# 2014_FDP_PROPULSION.net
KiCad netlist of a schematic drawn in Altium Designer
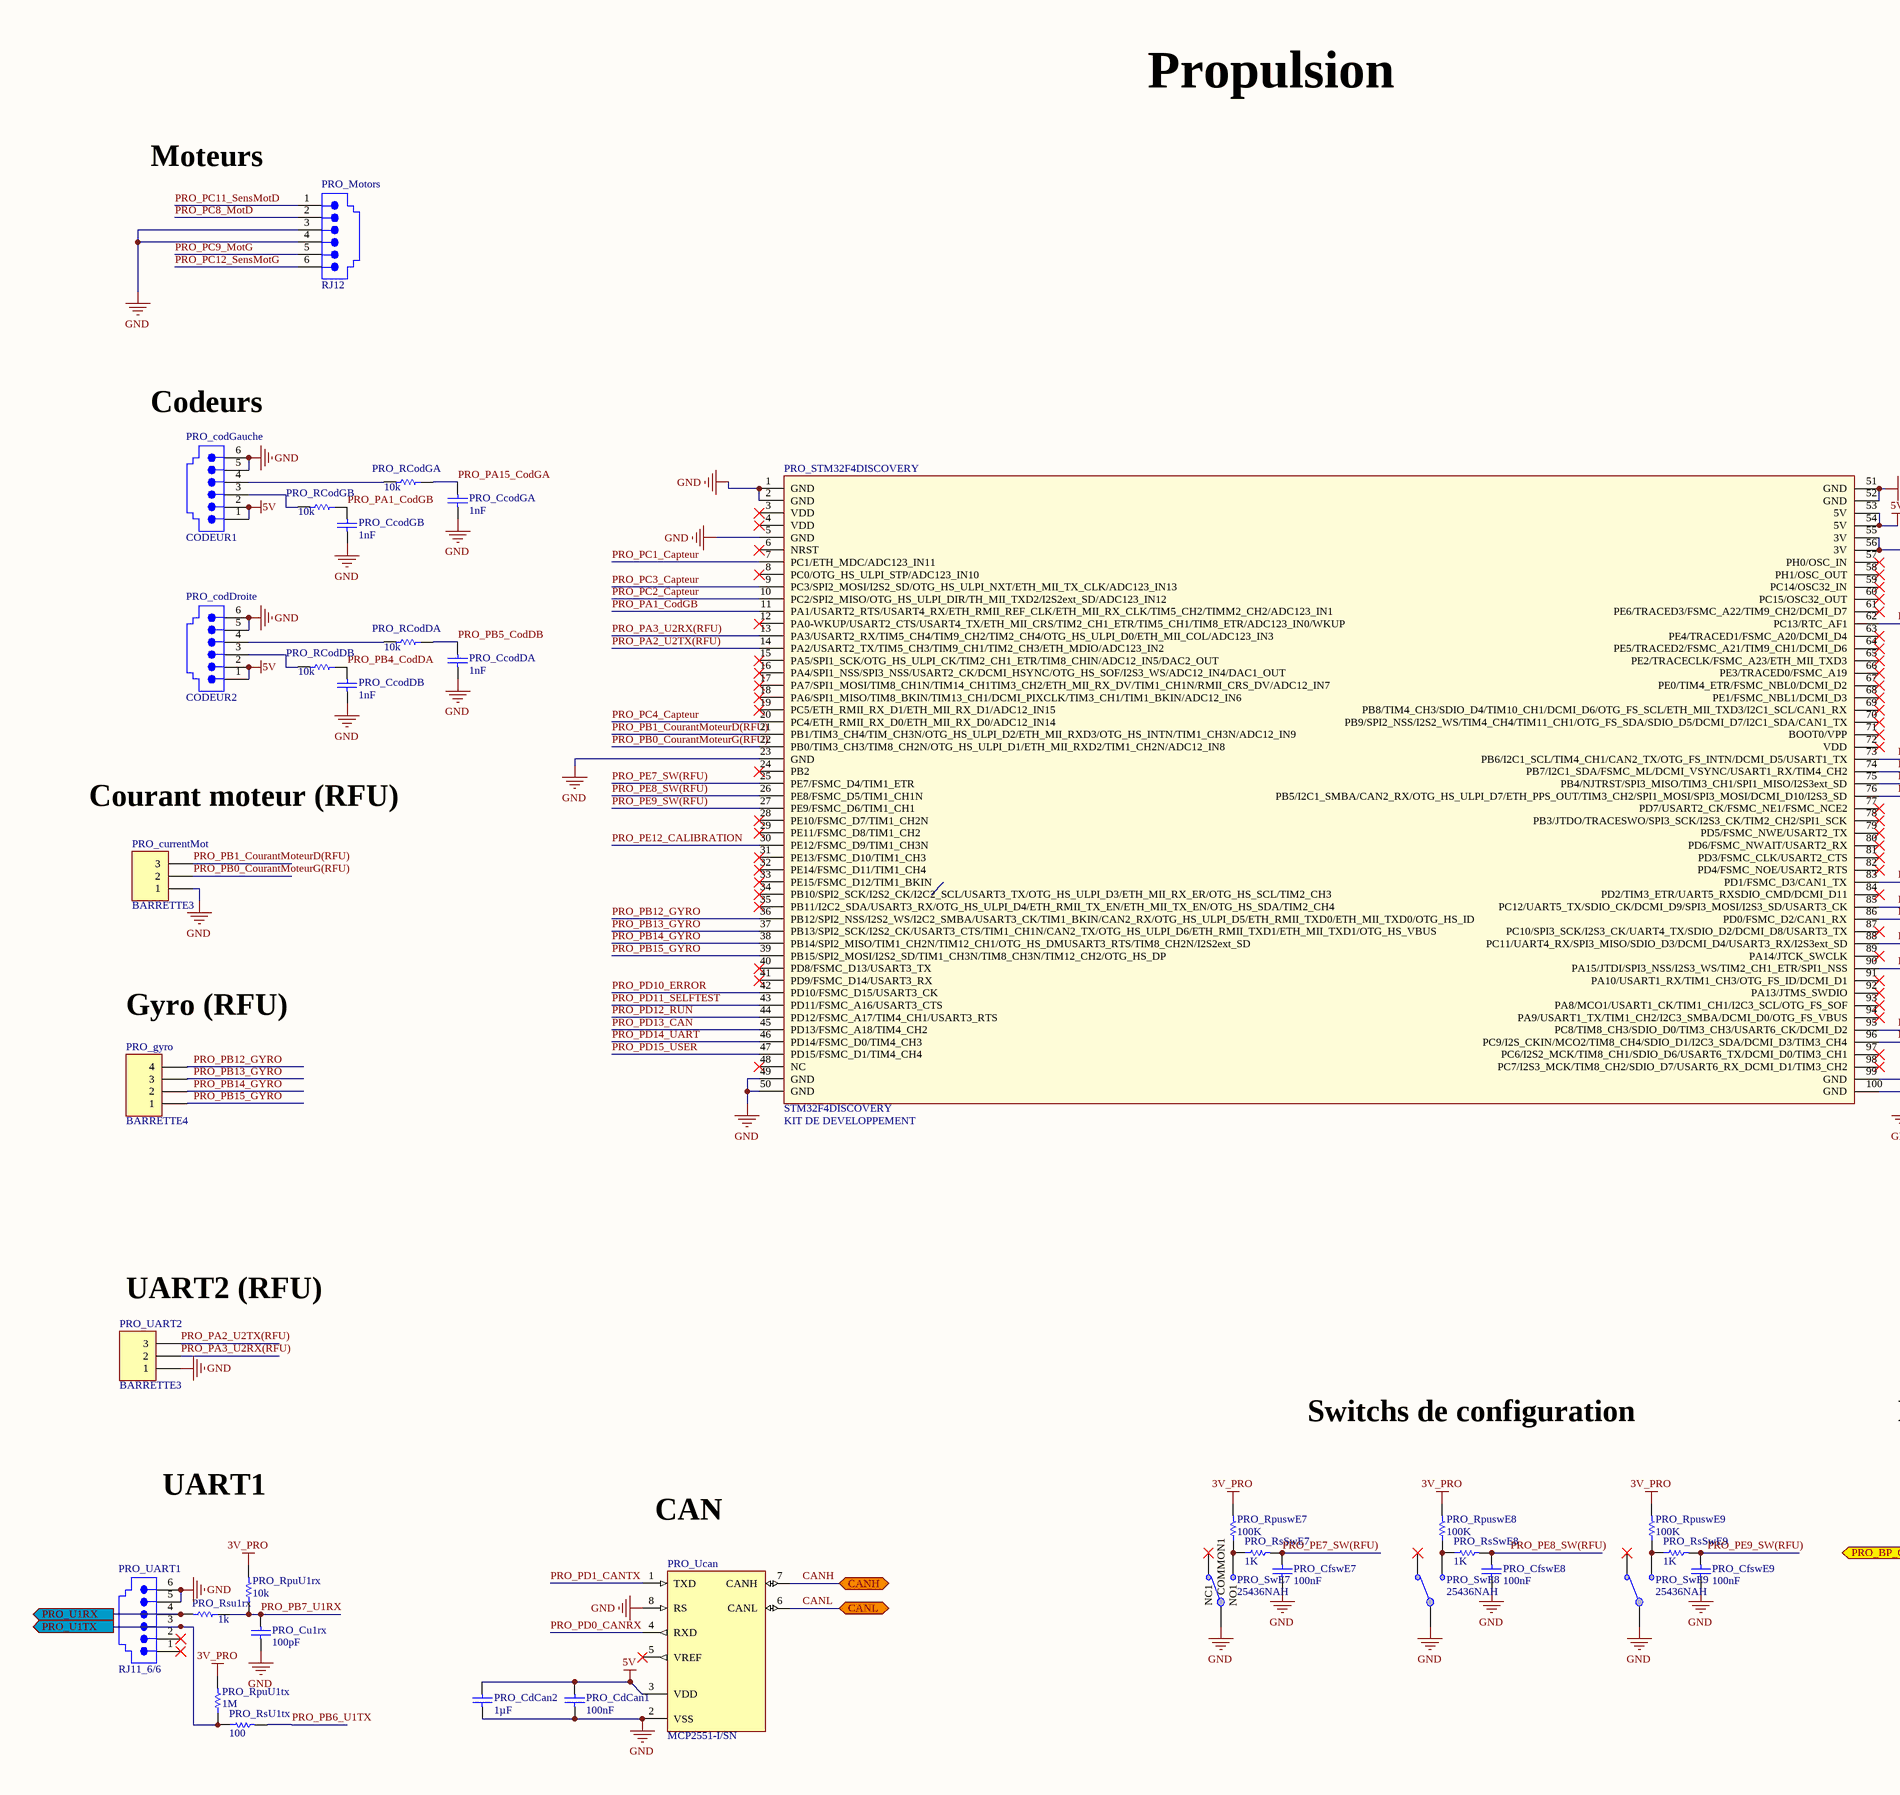
[diagram p0: 2014_FDP_PROPULSION.SchDoc, left]
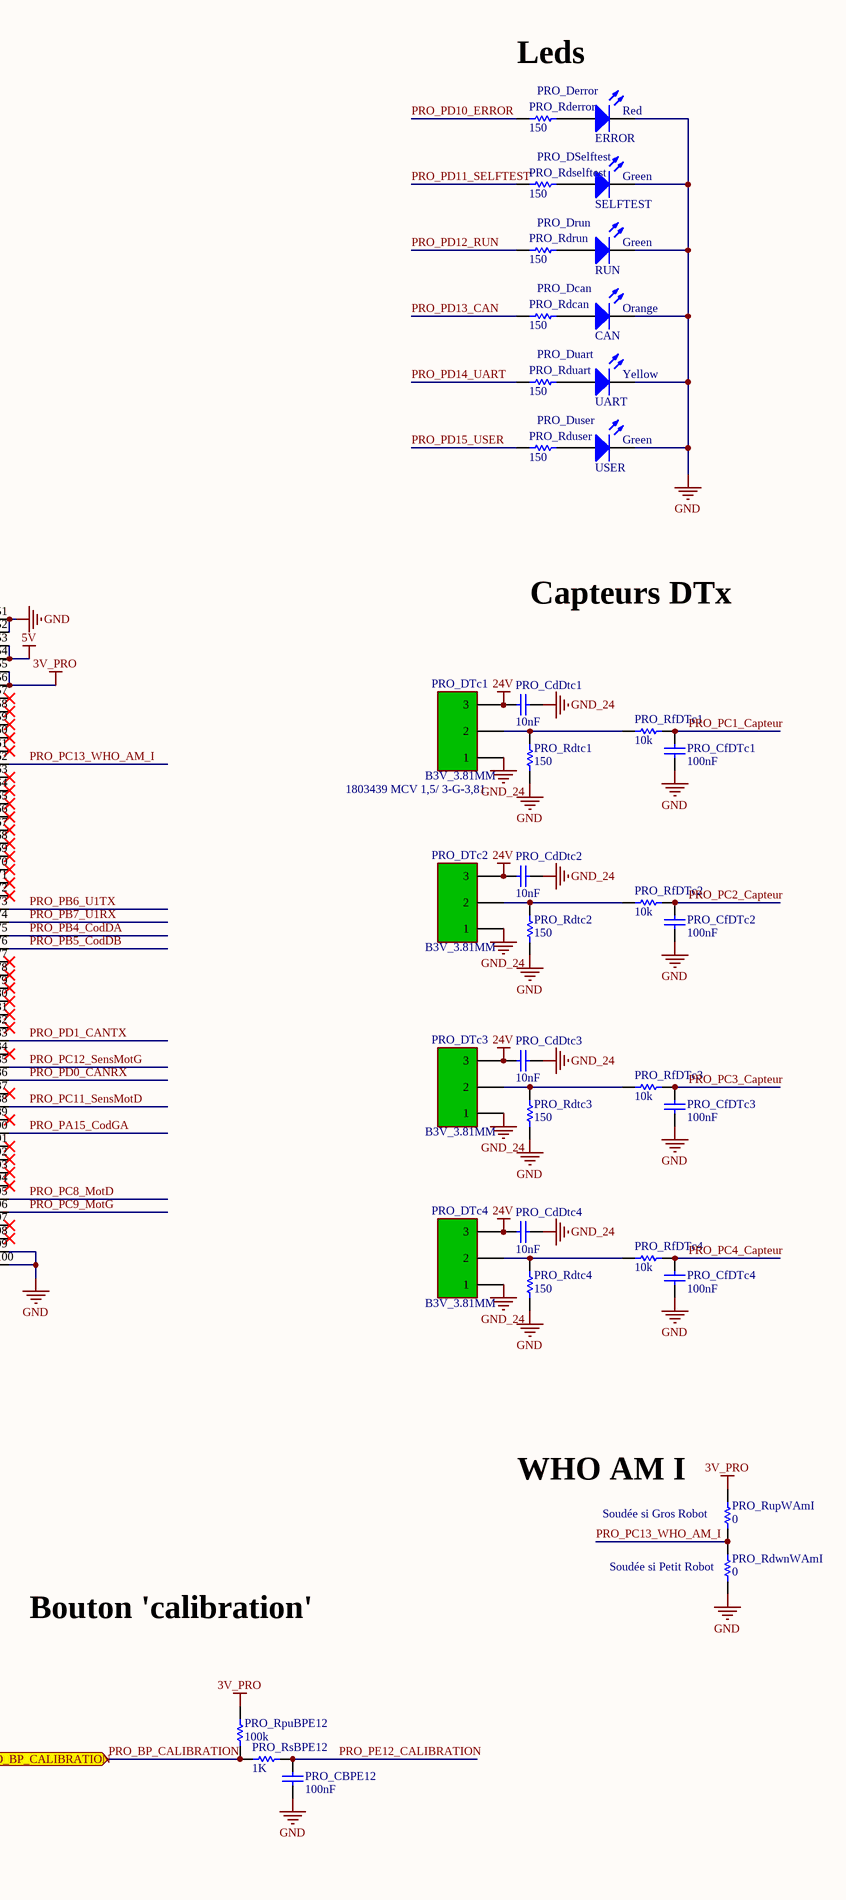
[diagram p1: 2014_FDP_PROPULSION.SchDoc, right]

(export (version "E")
  (design (tool "Eeschema 10.0.6"))
  (components
    (comp (ref "PRO_CBPE12")
      (value "100nF")
      (footprint "C0805_N")
      (description "Capacitor")
      (fields (field (name "PUBLISHER") "Altium Limited"))
      (libsource (lib "_ROBOT") (part "Condensateur"))
    )
    (comp (ref "PRO_CcodDA")
      (value "1nF")
      (footprint "C0805_N")
      (description "Capacitor")
      (fields (field (name "PUBLISHER") "Altium Limited"))
      (libsource (lib "_ROBOT") (part "Condensateur"))
    )
    (comp (ref "PRO_CcodDB")
      (value "1nF")
      (footprint "C0805_N")
      (description "Capacitor")
      (fields (field (name "PUBLISHER") "Altium Limited"))
      (libsource (lib "_ROBOT") (part "Condensateur"))
    )
    (comp (ref "PRO_CcodGA")
      (value "1nF")
      (footprint "C0805_N")
      (description "Capacitor")
      (fields (field (name "PUBLISHER") "Altium Limited"))
      (libsource (lib "_ROBOT") (part "Condensateur"))
    )
    (comp (ref "PRO_CcodGB")
      (value "1nF")
      (footprint "C0805_N")
      (description "Capacitor")
      (fields (field (name "PUBLISHER") "Altium Limited"))
      (libsource (lib "_ROBOT") (part "Condensateur"))
    )
    (comp (ref "PRO_CdCan1")
      (value "100nF")
      (footprint "C0805_N")
      (description "Capacitor")
      (fields (field (name "PUBLISHER") "Altium Limited"))
      (libsource (lib "_ROBOT") (part "Condensateur"))
    )
    (comp (ref "PRO_CdCan2")
      (value "1µF")
      (footprint "C0805_N")
      (description "Capacitor")
      (fields (field (name "PUBLISHER") "Altium Limited"))
      (libsource (lib "_ROBOT") (part "Condensateur"))
    )
    (comp (ref "PRO_CdDtc1")
      (value "10nF")
      (footprint "C0805_N")
      (description "Capacitor")
      (fields (field (name "PUBLISHER") "Altium Limited"))
      (libsource (lib "_ROBOT") (part "Condensateur"))
    )
    (comp (ref "PRO_CdDtc2")
      (value "10nF")
      (footprint "C0805_N")
      (description "Capacitor")
      (fields (field (name "PUBLISHER") "Altium Limited"))
      (libsource (lib "_ROBOT") (part "Condensateur"))
    )
    (comp (ref "PRO_CdDtc3")
      (value "10nF")
      (footprint "C0805_N")
      (description "Capacitor")
      (fields (field (name "PUBLISHER") "Altium Limited"))
      (libsource (lib "_ROBOT") (part "Condensateur"))
    )
    (comp (ref "PRO_CdDtc4")
      (value "10nF")
      (footprint "C0805_N")
      (description "Capacitor")
      (fields (field (name "PUBLISHER") "Altium Limited"))
      (libsource (lib "_ROBOT") (part "Condensateur"))
    )
    (comp (ref "PRO_CfDTc1")
      (value "100nF")
      (footprint "C0805_N")
      (description "Capacitor")
      (fields (field (name "PUBLISHER") "Altium Limited"))
      (libsource (lib "_ROBOT") (part "Condensateur"))
    )
    (comp (ref "PRO_CfDTc2")
      (value "100nF")
      (footprint "C0805_N")
      (description "Capacitor")
      (fields (field (name "PUBLISHER") "Altium Limited"))
      (libsource (lib "_ROBOT") (part "Condensateur"))
    )
    (comp (ref "PRO_CfDTc3")
      (value "100nF")
      (footprint "C0805_N")
      (description "Capacitor")
      (fields (field (name "PUBLISHER") "Altium Limited"))
      (libsource (lib "_ROBOT") (part "Condensateur"))
    )
    (comp (ref "PRO_CfDTc4")
      (value "100nF")
      (footprint "C0805_N")
      (description "Capacitor")
      (fields (field (name "PUBLISHER") "Altium Limited"))
      (libsource (lib "_ROBOT") (part "Condensateur"))
    )
    (comp (ref "PRO_CfswE7")
      (value "100nF")
      (footprint "C0805_N")
      (description "Capacitor")
      (fields (field (name "PUBLISHER") "Altium Limited"))
      (libsource (lib "_ROBOT") (part "Condensateur"))
    )
    (comp (ref "PRO_CfswE8")
      (value "100nF")
      (footprint "C0805_N")
      (description "Capacitor")
      (fields (field (name "PUBLISHER") "Altium Limited"))
      (libsource (lib "_ROBOT") (part "Condensateur"))
    )
    (comp (ref "PRO_CfswE9")
      (value "100nF")
      (footprint "C0805_N")
      (description "Capacitor")
      (fields (field (name "PUBLISHER") "Altium Limited"))
      (libsource (lib "_ROBOT") (part "Condensateur"))
    )
    (comp (ref "PRO_codDroite")
      (value "CODEUR2")
      (footprint "RJ11_6/6 - droit")
      (description "Right Angle, Standard Profile, Offset Latch DECconnect, Flangeless PCB Jack")
      (fields (field (name "PUBLISHER") "Altium Limited"))
      (libsource (lib "miniprojet") (part "RJ11_6/6"))
    )
    (comp (ref "PRO_codGauche")
      (value "CODEUR1")
      (footprint "RJ11_6/6 - droit")
      (description "Right Angle, Standard Profile, Offset Latch DECconnect, Flangeless PCB Jack")
      (fields (field (name "PUBLISHER") "Altium Limited"))
      (libsource (lib "miniprojet") (part "RJ11_6/6"))
    )
    (comp (ref "PRO_Cu1rx")
      (value "100pF")
      (footprint "C0805_N")
      (description "Capacitor")
      (fields (field (name "PUBLISHER") "Altium Limited"))
      (libsource (lib "_ROBOT") (part "Condensateur"))
    )
    (comp (ref "PRO_currentMot")
      (value "BARRETTE3")
      (footprint "HE14_3")
      (description "Header, 3-Pin")
      (fields (field (name "PUBLISHER") "Altium Limited"))
      (libsource (lib "Connecteur") (part "BARRETTE3"))
    )
    (comp (ref "PRO_Dcan")
      (value "CAN")
      (footprint "LED_0805")
      (description "Typical LED")
      (fields (field (name "PUBLISHER") "Altium Limited"))
      (libsource (lib "_ROBOT") (part "LED"))
    )
    (comp (ref "PRO_Derror")
      (value "ERROR")
      (footprint "LED_0805")
      (description "Typical LED")
      (fields (field (name "PUBLISHER") "Altium Limited"))
      (libsource (lib "_ROBOT") (part "LED"))
    )
    (comp (ref "PRO_Drun")
      (value "RUN")
      (footprint "LED_0805")
      (description "Typical LED")
      (fields (field (name "PUBLISHER") "Altium Limited"))
      (libsource (lib "_ROBOT") (part "LED"))
    )
    (comp (ref "PRO_DSelftest")
      (value "SELFTEST")
      (footprint "LED_0805")
      (description "Typical LED")
      (fields (field (name "PUBLISHER") "Altium Limited"))
      (libsource (lib "_ROBOT") (part "LED"))
    )
    (comp (ref "PRO_DTc1")
      (value "B3V_3.81MM")
      (footprint "BORNIER_3V_3.81MM")
      (fields (field (name "REF") "1803439 MCV 1,5/ 3-G-3,81"))
      (libsource (lib "Connecteur") (part "BORNIER_3V_3.81MM"))
    )
    (comp (ref "PRO_DTc2")
      (value "B3V_3.81MM")
      (footprint "BORNIER_3V_3.81MM")
      (libsource (lib "Connecteur") (part "BORNIER_3V_3.81MM"))
    )
    (comp (ref "PRO_DTc3")
      (value "B3V_3.81MM")
      (footprint "BORNIER_3V_3.81MM")
      (libsource (lib "Connecteur") (part "BORNIER_3V_3.81MM"))
    )
    (comp (ref "PRO_DTc4")
      (value "B3V_3.81MM")
      (footprint "BORNIER_3V_3.81MM")
      (libsource (lib "Connecteur") (part "BORNIER_3V_3.81MM"))
    )
    (comp (ref "PRO_Duart")
      (value "UART")
      (footprint "LED_0805")
      (description "Typical LED")
      (fields (field (name "PUBLISHER") "Altium Limited"))
      (libsource (lib "_ROBOT") (part "LED"))
    )
    (comp (ref "PRO_Duser")
      (value "USER")
      (footprint "LED_0805")
      (description "Typical LED")
      (fields (field (name "PUBLISHER") "Altium Limited"))
      (libsource (lib "_ROBOT") (part "LED"))
    )
    (comp (ref "PRO_gyro")
      (value "BARRETTE4")
      (footprint "HE14_4")
      (description "Header, 4-Pin")
      (fields (field (name "PUBLISHER") "Altium Limited"))
      (libsource (lib "Connecteur") (part "BARRETTE4"))
    )
    (comp (ref "PRO_Motors")
      (value "RJ12")
      (footprint "RJ11_6/6")
      (description "Right Angle, Standard Profile, Offset Latch DECconnect, Flangeless PCB Jack")
      (fields (field (name "PUBLISHER") "Altium Limited"))
      (libsource (lib "Connecteur") (part "RJ11_6/6"))
    )
    (comp (ref "PRO_RCodDA")
      (value "10k")
      (footprint "R1206_N")
      (description "Resistor")
      (fields (field (name "PUBLISHER") "Altium Limited"))
      (libsource (lib "_ROBOT") (part "Resistor"))
    )
    (comp (ref "PRO_RCodDB")
      (value "10k")
      (footprint "R1206_N")
      (description "Resistor")
      (fields (field (name "PUBLISHER") "Altium Limited"))
      (libsource (lib "_ROBOT") (part "Resistor"))
    )
    (comp (ref "PRO_RCodGA")
      (value "10k")
      (footprint "R1206_N")
      (description "Resistor")
      (fields (field (name "PUBLISHER") "Altium Limited"))
      (libsource (lib "_ROBOT") (part "Resistor"))
    )
    (comp (ref "PRO_RCodGB")
      (value "10k")
      (footprint "R1206_N")
      (description "Resistor")
      (fields (field (name "PUBLISHER") "Altium Limited"))
      (libsource (lib "_ROBOT") (part "Resistor"))
    )
    (comp (ref "PRO_Rdcan")
      (value "150")
      (footprint "R1206_N")
      (description "Resistor")
      (fields (field (name "PUBLISHER") "Altium Limited"))
      (libsource (lib "_ROBOT") (part "Resistor"))
    )
    (comp (ref "PRO_Rderror")
      (value "150")
      (footprint "R1206_N")
      (description "Resistor")
      (fields (field (name "PUBLISHER") "Altium Limited"))
      (libsource (lib "_ROBOT") (part "Resistor"))
    )
    (comp (ref "PRO_Rdrun")
      (value "150")
      (footprint "R1206_N")
      (description "Resistor")
      (fields (field (name "PUBLISHER") "Altium Limited"))
      (libsource (lib "_ROBOT") (part "Resistor"))
    )
    (comp (ref "PRO_Rdselftest")
      (value "150")
      (footprint "R1206_N")
      (description "Resistor")
      (fields (field (name "PUBLISHER") "Altium Limited"))
      (libsource (lib "_ROBOT") (part "Resistor"))
    )
    (comp (ref "PRO_Rdtc1")
      (value "150")
      (footprint "R1206_N")
      (description "Resistor")
      (fields (field (name "PUBLISHER") "Altium Limited"))
      (libsource (lib "_ROBOT") (part "Resistor"))
    )
    (comp (ref "PRO_Rdtc2")
      (value "150")
      (footprint "R1206_N")
      (description "Resistor")
      (fields (field (name "PUBLISHER") "Altium Limited"))
      (libsource (lib "_ROBOT") (part "Resistor"))
    )
    (comp (ref "PRO_Rdtc3")
      (value "150")
      (footprint "R1206_N")
      (description "Resistor")
      (fields (field (name "PUBLISHER") "Altium Limited"))
      (libsource (lib "_ROBOT") (part "Resistor"))
    )
    (comp (ref "PRO_Rdtc4")
      (value "150")
      (footprint "R1206_N")
      (description "Resistor")
      (fields (field (name "PUBLISHER") "Altium Limited"))
      (libsource (lib "_ROBOT") (part "Resistor"))
    )
    (comp (ref "PRO_Rduart")
      (value "150")
      (footprint "R1206_N")
      (description "Resistor")
      (fields (field (name "PUBLISHER") "Altium Limited"))
      (libsource (lib "_ROBOT") (part "Resistor"))
    )
    (comp (ref "PRO_Rduser")
      (value "150")
      (footprint "R1206_N")
      (description "Resistor")
      (fields (field (name "PUBLISHER") "Altium Limited"))
      (libsource (lib "_ROBOT") (part "Resistor"))
    )
    (comp (ref "PRO_RdwnWAmI")
      (value "0")
      (footprint "R1206_N")
      (description "Resistor")
      (fields (field (name "PUBLISHER") "Altium Limited"))
      (libsource (lib "_ROBOT") (part "Resistor"))
    )
    (comp (ref "PRO_RfDTc1")
      (value "10k")
      (footprint "R1206_N")
      (description "Resistor")
      (fields (field (name "PUBLISHER") "Altium Limited"))
      (libsource (lib "_ROBOT") (part "Resistor"))
    )
    (comp (ref "PRO_RfDTc2")
      (value "10k")
      (footprint "R1206_N")
      (description "Resistor")
      (fields (field (name "PUBLISHER") "Altium Limited"))
      (libsource (lib "_ROBOT") (part "Resistor"))
    )
    (comp (ref "PRO_RfDTc3")
      (value "10k")
      (footprint "R1206_N")
      (description "Resistor")
      (fields (field (name "PUBLISHER") "Altium Limited"))
      (libsource (lib "_ROBOT") (part "Resistor"))
    )
    (comp (ref "PRO_RfDTc4")
      (value "10k")
      (footprint "R1206_N")
      (description "Resistor")
      (fields (field (name "PUBLISHER") "Altium Limited"))
      (libsource (lib "_ROBOT") (part "Resistor"))
    )
    (comp (ref "PRO_RpuBPE12")
      (value "100k")
      (footprint "R1206_N")
      (description "Resistor")
      (fields (field (name "PUBLISHER") "Altium Limited"))
      (libsource (lib "_ROBOT") (part "Resistor"))
    )
    (comp (ref "PRO_RpuswE7")
      (value "100K")
      (footprint "R1206_N")
      (description "Resistor")
      (fields (field (name "PUBLISHER") "Altium Limited"))
      (libsource (lib "_ROBOT") (part "Resistor"))
    )
    (comp (ref "PRO_RpuswE8")
      (value "100K")
      (footprint "R1206_N")
      (description "Resistor")
      (fields (field (name "PUBLISHER") "Altium Limited"))
      (libsource (lib "_ROBOT") (part "Resistor"))
    )
    (comp (ref "PRO_RpuswE9")
      (value "100K")
      (footprint "R1206_N")
      (description "Resistor")
      (fields (field (name "PUBLISHER") "Altium Limited"))
      (libsource (lib "_ROBOT") (part "Resistor"))
    )
    (comp (ref "PRO_RpuU1rx")
      (value "10k")
      (footprint "R1206_N")
      (description "Resistor")
      (fields (field (name "PUBLISHER") "Altium Limited"))
      (libsource (lib "_ROBOT") (part "Resistor"))
    )
    (comp (ref "PRO_RpuU1tx")
      (value "1M")
      (footprint "R1206_N")
      (description "Resistor")
      (fields (field (name "PUBLISHER") "Altium Limited"))
      (libsource (lib "_ROBOT") (part "Resistor"))
    )
    (comp (ref "PRO_RsBPE12")
      (value "1K")
      (footprint "R1206_N")
      (description "Resistor")
      (fields (field (name "PUBLISHER") "Altium Limited"))
      (libsource (lib "_ROBOT") (part "Resistor"))
    )
    (comp (ref "PRO_RsSwE7")
      (value "1K")
      (footprint "R1206_N")
      (description "Resistor")
      (fields (field (name "PUBLISHER") "Altium Limited"))
      (libsource (lib "_ROBOT") (part "Resistor"))
    )
    (comp (ref "PRO_RsSwE8")
      (value "1K")
      (footprint "R1206_N")
      (description "Resistor")
      (fields (field (name "PUBLISHER") "Altium Limited"))
      (libsource (lib "_ROBOT") (part "Resistor"))
    )
    (comp (ref "PRO_RsSwE9")
      (value "1K")
      (footprint "R1206_N")
      (description "Resistor")
      (fields (field (name "PUBLISHER") "Altium Limited"))
      (libsource (lib "_ROBOT") (part "Resistor"))
    )
    (comp (ref "PRO_Rsu1rx")
      (value "1k")
      (footprint "R1206_N")
      (description "Resistor")
      (fields (field (name "PUBLISHER") "Altium Limited"))
      (libsource (lib "_ROBOT") (part "Resistor"))
    )
    (comp (ref "PRO_RsU1tx")
      (value "100")
      (footprint "R1206_N")
      (description "Resistor")
      (fields (field (name "PUBLISHER") "Altium Limited"))
      (libsource (lib "_ROBOT") (part "Resistor"))
    )
    (comp (ref "PRO_RupWAmI")
      (value "0")
      (footprint "R1206_N")
      (description "Resistor")
      (fields (field (name "PUBLISHER") "Altium Limited"))
      (libsource (lib "_ROBOT") (part "Resistor"))
    )
    (comp (ref "PRO_STM32F4DISCOVERY")
      (value "STM32F4DISCOVERY")
      (footprint "STM32_F4DISCOVERY")
      (description "KIT DE DEVELOPPEMENT POUR MICROCONTROLEUR STM32F407VGT6")
      (fields (field (name "TYPE") "KIT DE DEVELOPPEMENT"))
      (libsource (lib "circuits integres") (part "STM32F4DISCOVERY"))
    )
    (comp (ref "PRO_SwE7")
      (value "25436NAH")
      (footprint "SW_UNIPOL_DROIT - APEM 18235")
      (description "Switch unipolaire a levier")
      (libsource (lib "_ROBOT") (part "SW SPDT- APEM Série 523x"))
    )
    (comp (ref "PRO_SwE8")
      (value "25436NAH")
      (footprint "SW_UNIPOL_DROIT - APEM 18235")
      (description "Switch unipolaire a levier")
      (libsource (lib "") (part "SW SPDT- APEM Série 523x_1"))
    )
    (comp (ref "PRO_SwE9")
      (value "25436NAH")
      (footprint "SW_UNIPOL_DROIT - APEM 18235")
      (description "Switch unipolaire a levier")
      (libsource (lib "") (part "SW SPDT- APEM Série 523x_1"))
    )
    (comp (ref "PRO_UART1")
      (value "RJ11_6/6")
      (footprint "RJ11_6/6")
      (description "Right Angle, Standard Profile, Offset Latch DECconnect, Flangeless PCB Jack")
      (fields (field (name "PUBLISHER") "Altium Limited"))
      (libsource (lib "Connecteur") (part "RJ11_6/6"))
    )
    (comp (ref "PRO_UART2")
      (value "BARRETTE3")
      (footprint "HE14_3")
      (description "Header, 3-Pin")
      (fields (field (name "PUBLISHER") "Altium Limited"))
      (libsource (lib "Connecteur") (part "BARRETTE3"))
    )
    (comp (ref "PRO_Ucan")
      (value "MCP2551-I/SN")
      (footprint "SO8_N")
      (description "High-Speed CAN Transceiver, 8-Pin SOIC, Industrial Temperature")
      (fields (field (name "PUBLISHER") "Damien Guitton"))
      (libsource (lib "Circuit intégré") (part "MCP2551-I/SN"))
    )
  )
  (nets
    (net (code "1") (name "/CANH") (class "Default")
      (node (ref "PRO_Ucan") (pin "7") (pinfunction "CANH_7") (pintype "bidirectional"))
    )
    (net (code "2") (name "/CANL") (class "Default")
      (node (ref "PRO_Ucan") (pin "6") (pinfunction "CANL_6") (pintype "bidirectional"))
    )
    (net (code "3") (name "/PRO_BP_CALIBRATION") (class "Default")
      (node (ref "PRO_RpuBPE12") (pin "1") (pinfunction "1_1") (pintype "passive"))
      (node (ref "PRO_RsBPE12") (pin "1") (pinfunction "1_1") (pintype "passive"))
    )
    (net (code "4") (name "/PRO_PA1_CodGB") (class "Default")
      (node (ref "PRO_CcodGB") (pin "2") (pinfunction "2_2") (pintype "passive"))
      (node (ref "PRO_RCodGB") (pin "1") (pinfunction "1_1") (pintype "passive"))
      (node (ref "PRO_STM32F4DISCOVERY") (pin "11") (pinfunction "PA1/USART2_RTS/USART4_RX/ETH_RMII_REF_CLK/ETH_MII_RX_CLK/TIM5_CH2/TIMM2_CH2/ADC123_IN1_11") (pintype "passive"))
    )
    (net (code "5") (name "/PRO_PA2_U2TX(RFU)") (class "Default")
      (node (ref "PRO_STM32F4DISCOVERY") (pin "14") (pinfunction "PA2/USART2_TX/TIM5_CH3/TIM9_CH1/TIM2_CH3/ETH_MDIO/ADC123_IN2_14") (pintype "passive"))
      (node (ref "PRO_UART2") (pin "3") (pinfunction "3_3") (pintype "passive"))
    )
    (net (code "6") (name "/PRO_PA3_U2RX(RFU)") (class "Default")
      (node (ref "PRO_STM32F4DISCOVERY") (pin "13") (pinfunction "PA3/USART2_RX/TIM5_CH4/TIM9_CH2/TIM2_CH4/OTG_HS_ULPI_D0/ETH_MII_COL/ADC123_IN3_13") (pintype "passive"))
      (node (ref "PRO_UART2") (pin "2") (pinfunction "2_2") (pintype "passive"))
    )
    (net (code "7") (name "/PRO_PA15_CodGA") (class "Default")
      (node (ref "PRO_CcodGA") (pin "2") (pinfunction "2_2") (pintype "passive"))
      (node (ref "PRO_RCodGA") (pin "1") (pinfunction "1_1") (pintype "passive"))
      (node (ref "PRO_STM32F4DISCOVERY") (pin "90") (pinfunction "PA15/JTDI/SPI3_NSS/I2S3_WS/TIM2_CH1_ETR/SPI1_NSS_90") (pintype "passive"))
    )
    (net (code "8") (name "/PRO_PB0_CourantMoteurG(RFU)") (class "Default")
      (node (ref "PRO_STM32F4DISCOVERY") (pin "22") (pinfunction "PB0/TIM3_CH3/TIM8_CH2N/OTG_HS_ULPI_D1/ETH_MII_RXD2/TIM1_CH2N/ADC12_IN8_22") (pintype "passive"))
      (node (ref "PRO_currentMot") (pin "2") (pinfunction "2_2") (pintype "passive"))
    )
    (net (code "9") (name "/PRO_PB1_CourantMoteurD(RFU)") (class "Default")
      (node (ref "PRO_STM32F4DISCOVERY") (pin "21") (pinfunction "PB1/TIM3_CH4/TIM_CH3N/OTG_HS_ULPI_D2/ETH_MII_RXD3/OTG_HS_INTN/TIM1_CH3N/ADC12_IN9_21") (pintype "passive"))
      (node (ref "PRO_currentMot") (pin "3") (pinfunction "3_3") (pintype "passive"))
    )
    (net (code "10") (name "/PRO_PB4_CodDA") (class "Default")
      (node (ref "PRO_CcodDB") (pin "2") (pinfunction "2_2") (pintype "passive"))
      (node (ref "PRO_RCodDB") (pin "1") (pinfunction "1_1") (pintype "passive"))
      (node (ref "PRO_STM32F4DISCOVERY") (pin "75") (pinfunction "PB4/NJTRST/SPI3_MISO/TIM3_CH1/SPI1_MISO/I2S3ext_SD_75") (pintype "passive"))
    )
    (net (code "11") (name "/PRO_PB5_CodDB") (class "Default")
      (node (ref "PRO_CcodDA") (pin "2") (pinfunction "2_2") (pintype "passive"))
      (node (ref "PRO_RCodDA") (pin "1") (pinfunction "1_1") (pintype "passive"))
      (node (ref "PRO_STM32F4DISCOVERY") (pin "76") (pinfunction "PB5/I2C1_SMBA/CAN2_RX/OTG_HS_ULPI_D7/ETH_PPS_OUT/TIM3_CH2/SPI1_MOSI/SPI3_MOSI/DCMI_D10/I2S3_SD_76") (pintype "passive"))
    )
    (net (code "12") (name "/PRO_PB6_U1TX") (class "Default")
      (node (ref "PRO_RsU1tx") (pin "2") (pinfunction "2_2") (pintype "passive"))
      (node (ref "PRO_STM32F4DISCOVERY") (pin "73") (pinfunction "PB6/I2C1_SCL/TIM4_CH1/CAN2_TX/OTG_FS_INTN/DCMI_D5/USART1_TX_73") (pintype "passive"))
    )
    (net (code "13") (name "/PRO_PB7_U1RX") (class "Default")
      (node (ref "PRO_Cu1rx") (pin "2") (pinfunction "2_2") (pintype "passive"))
      (node (ref "PRO_RpuU1rx") (pin "1") (pinfunction "1_1") (pintype "passive"))
      (node (ref "PRO_Rsu1rx") (pin "1") (pinfunction "1_1") (pintype "passive"))
      (node (ref "PRO_STM32F4DISCOVERY") (pin "74") (pinfunction "PB7/I2C1_SDA/FSMC_ML/DCMI_VSYNC/USART1_RX/TIM4_CH2_74") (pintype "passive"))
    )
    (net (code "14") (name "/PRO_PB12_GYRO") (class "Default")
      (node (ref "PRO_STM32F4DISCOVERY") (pin "36") (pinfunction "PB12/SPI2_NSS/I2S2_WS/I2C2_SMBA/USART3_CK/TIM1_BKIN/CAN2_RX/OTG_HS_ULPI_D5/ETH_RMII_TXD0/ETH_MII_TXD0/OTG_HS_ID_36") (pintype "passive"))
      (node (ref "PRO_gyro") (pin "4") (pinfunction "4_4") (pintype "passive"))
    )
    (net (code "15") (name "/PRO_PB13_GYRO") (class "Default")
      (node (ref "PRO_STM32F4DISCOVERY") (pin "37") (pinfunction "PB13/SPI2_SCK/I2S2_CK/USART3_CTS/TIM1_CH1N/CAN2_TX/OTG_HS_ULPI_D6/ETH_RMII_TXD1/ETH_MII_TXD1/OTG_HS_VBUS_37") (pintype "passive"))
      (node (ref "PRO_gyro") (pin "3") (pinfunction "3_3") (pintype "passive"))
    )
    (net (code "16") (name "/PRO_PB14_GYRO") (class "Default")
      (node (ref "PRO_STM32F4DISCOVERY") (pin "38") (pinfunction "PB14/SPI2_MISO/TIM1_CH2N/TIM12_CH1/OTG_HS_DMUSART3_RTS/TIM8_CH2N/I2S2ext_SD_38") (pintype "passive"))
      (node (ref "PRO_gyro") (pin "2") (pinfunction "2_2") (pintype "passive"))
    )
    (net (code "17") (name "/PRO_PB15_GYRO") (class "Default")
      (node (ref "PRO_STM32F4DISCOVERY") (pin "39") (pinfunction "PB15/SPI2_MOSI/I2S2_SD/TIM1_CH3N/TIM8_CH3N/TIM12_CH2/OTG_HS_DP_39") (pintype "passive"))
      (node (ref "PRO_gyro") (pin "1") (pinfunction "1_1") (pintype "passive"))
    )
    (net (code "18") (name "/PRO_PC1_Capteur") (class "Default")
      (node (ref "PRO_CfDTc1") (pin "2") (pinfunction "2_2") (pintype "passive"))
      (node (ref "PRO_RfDTc1") (pin "2") (pinfunction "2_2") (pintype "passive"))
      (node (ref "PRO_STM32F4DISCOVERY") (pin "7") (pinfunction "PC1/ETH_MDC/ADC123_IN11_7") (pintype "passive"))
    )
    (net (code "19") (name "/PRO_PC2_Capteur") (class "Default")
      (node (ref "PRO_CfDTc2") (pin "2") (pinfunction "2_2") (pintype "passive"))
      (node (ref "PRO_RfDTc2") (pin "2") (pinfunction "2_2") (pintype "passive"))
      (node (ref "PRO_STM32F4DISCOVERY") (pin "10") (pinfunction "PC2/SPI2_MISO/OTG_HS_ULPI_DIR/TH_MII_TXD2/I2S2ext_SD/ADC123_IN12_10") (pintype "passive"))
    )
    (net (code "20") (name "/PRO_PC3_Capteur") (class "Default")
      (node (ref "PRO_CfDTc3") (pin "2") (pinfunction "2_2") (pintype "passive"))
      (node (ref "PRO_RfDTc3") (pin "2") (pinfunction "2_2") (pintype "passive"))
      (node (ref "PRO_STM32F4DISCOVERY") (pin "9") (pinfunction "PC3/SPI2_MOSI/I2S2_SD/OTG_HS_ULPI_NXT/ETH_MII_TX_CLK/ADC123_IN13_9") (pintype "passive"))
    )
    (net (code "21") (name "/PRO_PC4_Capteur") (class "Default")
      (node (ref "PRO_CfDTc4") (pin "2") (pinfunction "2_2") (pintype "passive"))
      (node (ref "PRO_RfDTc4") (pin "2") (pinfunction "2_2") (pintype "passive"))
      (node (ref "PRO_STM32F4DISCOVERY") (pin "20") (pinfunction "PC4/ETH_RMII_RX_D0/ETH_MII_RX_D0/ADC12_IN14_20") (pintype "passive"))
    )
    (net (code "22") (name "/PRO_PC8_MotD") (class "Default")
      (node (ref "PRO_Motors") (pin "2") (pinfunction "2_2") (pintype "passive"))
      (node (ref "PRO_STM32F4DISCOVERY") (pin "95") (pinfunction "PC8/TIM8_CH3/SDIO_D0/TIM3_CH3/USART6_CK/DCMI_D2_95") (pintype "passive"))
    )
    (net (code "23") (name "/PRO_PC9_MotG") (class "Default")
      (node (ref "PRO_Motors") (pin "5") (pinfunction "5_5") (pintype "passive"))
      (node (ref "PRO_STM32F4DISCOVERY") (pin "96") (pinfunction "PC9/I2S_CKIN/MCO2/TIM8_CH4/SDIO_D1/I2C3_SDA/DCMI_D3/TIM3_CH4_96") (pintype "passive"))
    )
    (net (code "24") (name "/PRO_PC11_SensMotD") (class "Default")
      (node (ref "PRO_Motors") (pin "1") (pinfunction "1_1") (pintype "passive"))
      (node (ref "PRO_STM32F4DISCOVERY") (pin "88") (pinfunction "PC11/UART4_RX/SPI3_MISO/SDIO_D3/DCMI_D4/USART3_RX/I2S3ext_SD_88") (pintype "passive"))
    )
    (net (code "25") (name "/PRO_PC12_SensMotG") (class "Default")
      (node (ref "PRO_Motors") (pin "6") (pinfunction "6_6") (pintype "passive"))
      (node (ref "PRO_STM32F4DISCOVERY") (pin "85") (pinfunction "PC12/UART5_TX/SDIO_CK/DCMI_D9/SPI3_MOSI/I2S3_SD/USART3_CK_85") (pintype "passive"))
    )
    (net (code "26") (name "/PRO_PC13_WHO_AM_I") (class "Default")
      (node (ref "PRO_RdwnWAmI") (pin "2") (pinfunction "2_2") (pintype "passive"))
      (node (ref "PRO_RupWAmI") (pin "1") (pinfunction "1_1") (pintype "passive"))
      (node (ref "PRO_STM32F4DISCOVERY") (pin "62") (pinfunction "PC13/RTC_AF1_62") (pintype "passive"))
    )
    (net (code "27") (name "/PRO_PD0_CANRX") (class "Default")
      (node (ref "PRO_STM32F4DISCOVERY") (pin "86") (pinfunction "PD0/FSMC_D2/CAN1_RX_86") (pintype "passive"))
      (node (ref "PRO_Ucan") (pin "4") (pinfunction "RXD_4") (pintype "output"))
    )
    (net (code "28") (name "/PRO_PD1_CANTX") (class "Default")
      (node (ref "PRO_STM32F4DISCOVERY") (pin "83") (pinfunction "PD1/FSMC_D3/CAN1_TX_83") (pintype "passive"))
      (node (ref "PRO_Ucan") (pin "1") (pinfunction "TXD_1") (pintype "input"))
    )
    (net (code "29") (name "/PRO_PD10_ERROR") (class "Default")
      (node (ref "PRO_Rderror") (pin "1") (pinfunction "1_1") (pintype "passive"))
      (node (ref "PRO_STM32F4DISCOVERY") (pin "42") (pinfunction "PD10/FSMC_D15/USART3_CK_42") (pintype "passive"))
    )
    (net (code "30") (name "/PRO_PD11_SELFTEST") (class "Default")
      (node (ref "PRO_Rdselftest") (pin "1") (pinfunction "1_1") (pintype "passive"))
      (node (ref "PRO_STM32F4DISCOVERY") (pin "43") (pinfunction "PD11/FSMC_A16/USART3_CTS_43") (pintype "passive"))
    )
    (net (code "31") (name "/PRO_PD12_RUN") (class "Default")
      (node (ref "PRO_Rdrun") (pin "1") (pinfunction "1_1") (pintype "passive"))
      (node (ref "PRO_STM32F4DISCOVERY") (pin "44") (pinfunction "PD12/FSMC_A17/TIM4_CH1/USART3_RTS_44") (pintype "passive"))
    )
    (net (code "32") (name "/PRO_PD13_CAN") (class "Default")
      (node (ref "PRO_Rdcan") (pin "1") (pinfunction "1_1") (pintype "passive"))
      (node (ref "PRO_STM32F4DISCOVERY") (pin "45") (pinfunction "PD13/FSMC_A18/TIM4_CH2_45") (pintype "passive"))
    )
    (net (code "33") (name "/PRO_PD14_UART") (class "Default")
      (node (ref "PRO_Rduart") (pin "1") (pinfunction "1_1") (pintype "passive"))
      (node (ref "PRO_STM32F4DISCOVERY") (pin "46") (pinfunction "PD14/FSMC_D0/TIM4_CH3_46") (pintype "passive"))
    )
    (net (code "34") (name "/PRO_PD15_USER") (class "Default")
      (node (ref "PRO_Rduser") (pin "1") (pinfunction "1_1") (pintype "passive"))
      (node (ref "PRO_STM32F4DISCOVERY") (pin "47") (pinfunction "PD15/FSMC_D1/TIM4_CH4_47") (pintype "passive"))
    )
    (net (code "35") (name "/PRO_PE7_SW(RFU)") (class "Default")
      (node (ref "PRO_CfswE7") (pin "2") (pinfunction "2_2") (pintype "passive"))
      (node (ref "PRO_RsSwE7") (pin "2") (pinfunction "2_2") (pintype "passive"))
      (node (ref "PRO_STM32F4DISCOVERY") (pin "25") (pinfunction "PE7/FSMC_D4/TIM1_ETR_25") (pintype "passive"))
    )
    (net (code "36") (name "/PRO_PE8_SW(RFU)") (class "Default")
      (node (ref "PRO_CfswE8") (pin "2") (pinfunction "2_2") (pintype "passive"))
      (node (ref "PRO_RsSwE8") (pin "2") (pinfunction "2_2") (pintype "passive"))
      (node (ref "PRO_STM32F4DISCOVERY") (pin "26") (pinfunction "PE8/FSMC_D5/TIM1_CH1N_26") (pintype "passive"))
    )
    (net (code "37") (name "/PRO_PE9_SW(RFU)") (class "Default")
      (node (ref "PRO_CfswE9") (pin "2") (pinfunction "2_2") (pintype "passive"))
      (node (ref "PRO_RsSwE9") (pin "2") (pinfunction "2_2") (pintype "passive"))
      (node (ref "PRO_STM32F4DISCOVERY") (pin "27") (pinfunction "PE9/FSMC_D6/TIM1_CH1_27") (pintype "passive"))
    )
    (net (code "38") (name "/PRO_PE12_CALIBRATION") (class "Default")
      (node (ref "PRO_CBPE12") (pin "2") (pinfunction "2_2") (pintype "passive"))
      (node (ref "PRO_RsBPE12") (pin "2") (pinfunction "2_2") (pintype "passive"))
      (node (ref "PRO_STM32F4DISCOVERY") (pin "30") (pinfunction "PE12/FSMC_D9/TIM1_CH3N_30") (pintype "passive"))
    )
    (net (code "39") (name "/PRO_U1RX") (class "Default")
      (node (ref "PRO_Rsu1rx") (pin "2") (pinfunction "2_2") (pintype "passive"))
      (node (ref "PRO_UART1") (pin "4") (pinfunction "4_4") (pintype "passive"))
    )
    (net (code "40") (name "/PRO_U1TX") (class "Default")
      (node (ref "PRO_RpuU1tx") (pin "1") (pinfunction "1_1") (pintype "passive"))
      (node (ref "PRO_RsU1tx") (pin "1") (pinfunction "1_1") (pintype "passive"))
      (node (ref "PRO_UART1") (pin "3") (pinfunction "3_3") (pintype "passive"))
    )
    (net (code "41") (name "3V_PRO") (class "Default")
      (node (ref "PRO_RpuBPE12") (pin "2") (pinfunction "2_2") (pintype "passive"))
      (node (ref "PRO_RpuU1rx") (pin "2") (pinfunction "2_2") (pintype "passive"))
      (node (ref "PRO_RpuU1tx") (pin "2") (pinfunction "2_2") (pintype "passive"))
      (node (ref "PRO_RpuswE7") (pin "2") (pinfunction "2_2") (pintype "passive"))
      (node (ref "PRO_RpuswE8") (pin "2") (pinfunction "2_2") (pintype "passive"))
      (node (ref "PRO_RpuswE9") (pin "2") (pinfunction "2_2") (pintype "passive"))
      (node (ref "PRO_RupWAmI") (pin "2") (pinfunction "2_2") (pintype "passive"))
      (node (ref "PRO_STM32F4DISCOVERY") (pin "55") (pinfunction "3V_55") (pintype "passive"))
      (node (ref "PRO_STM32F4DISCOVERY") (pin "56") (pinfunction "3V_56") (pintype "passive"))
    )
    (net (code "42") (name "5V") (class "Default")
      (node (ref "PRO_CdCan1") (pin "2") (pinfunction "2_2") (pintype "passive"))
      (node (ref "PRO_CdCan2") (pin "2") (pinfunction "2_2") (pintype "passive"))
      (node (ref "PRO_STM32F4DISCOVERY") (pin "53") (pinfunction "5V_53") (pintype "passive"))
      (node (ref "PRO_STM32F4DISCOVERY") (pin "54") (pinfunction "5V_54") (pintype "passive"))
      (node (ref "PRO_Ucan") (pin "3") (pinfunction "VDD_3") (pintype "power_in"))
      (node (ref "PRO_codDroite") (pin "1") (pinfunction "1_1") (pintype "passive"))
      (node (ref "PRO_codDroite") (pin "2") (pinfunction "2_2") (pintype "passive"))
      (node (ref "PRO_codGauche") (pin "1") (pinfunction "1_1") (pintype "passive"))
      (node (ref "PRO_codGauche") (pin "2") (pinfunction "2_2") (pintype "passive"))
    )
    (net (code "43") (name "24V") (class "Default")
      (node (ref "PRO_CdDtc1") (pin "2") (pinfunction "2_2") (pintype "passive"))
      (node (ref "PRO_CdDtc2") (pin "2") (pinfunction "2_2") (pintype "passive"))
      (node (ref "PRO_CdDtc3") (pin "2") (pinfunction "2_2") (pintype "passive"))
      (node (ref "PRO_CdDtc4") (pin "2") (pinfunction "2_2") (pintype "passive"))
      (node (ref "PRO_DTc1") (pin "3") (pinfunction "3_3") (pintype "passive"))
      (node (ref "PRO_DTc2") (pin "3") (pinfunction "3_3") (pintype "passive"))
      (node (ref "PRO_DTc3") (pin "3") (pinfunction "3_3") (pintype "passive"))
      (node (ref "PRO_DTc4") (pin "3") (pinfunction "3_3") (pintype "passive"))
    )
    (net (code "44") (name "GND") (class "Default")
      (node (ref "PRO_CBPE12") (pin "1") (pinfunction "1_1") (pintype "passive"))
      (node (ref "PRO_CcodDA") (pin "1") (pinfunction "1_1") (pintype "passive"))
      (node (ref "PRO_CcodDB") (pin "1") (pinfunction "1_1") (pintype "passive"))
      (node (ref "PRO_CcodGA") (pin "1") (pinfunction "1_1") (pintype "passive"))
      (node (ref "PRO_CcodGB") (pin "1") (pinfunction "1_1") (pintype "passive"))
      (node (ref "PRO_CdCan1") (pin "1") (pinfunction "1_1") (pintype "passive"))
      (node (ref "PRO_CdCan2") (pin "1") (pinfunction "1_1") (pintype "passive"))
      (node (ref "PRO_CfDTc1") (pin "1") (pinfunction "1_1") (pintype "passive"))
      (node (ref "PRO_CfDTc2") (pin "1") (pinfunction "1_1") (pintype "passive"))
      (node (ref "PRO_CfDTc3") (pin "1") (pinfunction "1_1") (pintype "passive"))
      (node (ref "PRO_CfDTc4") (pin "1") (pinfunction "1_1") (pintype "passive"))
      (node (ref "PRO_CfswE7") (pin "1") (pinfunction "1_1") (pintype "passive"))
      (node (ref "PRO_CfswE8") (pin "1") (pinfunction "1_1") (pintype "passive"))
      (node (ref "PRO_CfswE9") (pin "1") (pinfunction "1_1") (pintype "passive"))
      (node (ref "PRO_Cu1rx") (pin "1") (pinfunction "1_1") (pintype "passive"))
      (node (ref "PRO_DSelftest") (pin "2") (pinfunction "K_2") (pintype "passive"))
      (node (ref "PRO_Dcan") (pin "2") (pinfunction "K_2") (pintype "passive"))
      (node (ref "PRO_Derror") (pin "2") (pinfunction "K_2") (pintype "passive"))
      (node (ref "PRO_Drun") (pin "2") (pinfunction "K_2") (pintype "passive"))
      (node (ref "PRO_Duart") (pin "2") (pinfunction "K_2") (pintype "passive"))
      (node (ref "PRO_Duser") (pin "2") (pinfunction "K_2") (pintype "passive"))
      (node (ref "PRO_Motors") (pin "3") (pinfunction "3_3") (pintype "passive"))
      (node (ref "PRO_Motors") (pin "4") (pinfunction "4_4") (pintype "passive"))
      (node (ref "PRO_Rdtc1") (pin "1") (pinfunction "1_1") (pintype "passive"))
      (node (ref "PRO_Rdtc2") (pin "1") (pinfunction "1_1") (pintype "passive"))
      (node (ref "PRO_Rdtc3") (pin "1") (pinfunction "1_1") (pintype "passive"))
      (node (ref "PRO_Rdtc4") (pin "1") (pinfunction "1_1") (pintype "passive"))
      (node (ref "PRO_RdwnWAmI") (pin "1") (pinfunction "1_1") (pintype "passive"))
      (node (ref "PRO_STM32F4DISCOVERY") (pin "1") (pinfunction "GND_1") (pintype "passive"))
      (node (ref "PRO_STM32F4DISCOVERY") (pin "100") (pinfunction "GND_100") (pintype "passive"))
      (node (ref "PRO_STM32F4DISCOVERY") (pin "2") (pinfunction "GND_2") (pintype "passive"))
      (node (ref "PRO_STM32F4DISCOVERY") (pin "23") (pinfunction "GND_23") (pintype "passive"))
      (node (ref "PRO_STM32F4DISCOVERY") (pin "49") (pinfunction "GND_49") (pintype "passive"))
      (node (ref "PRO_STM32F4DISCOVERY") (pin "5") (pinfunction "GND_5") (pintype "passive"))
      (node (ref "PRO_STM32F4DISCOVERY") (pin "50") (pinfunction "GND_50") (pintype "passive"))
      (node (ref "PRO_STM32F4DISCOVERY") (pin "51") (pinfunction "GND_51") (pintype "passive"))
      (node (ref "PRO_STM32F4DISCOVERY") (pin "52") (pinfunction "GND_52") (pintype "passive"))
      (node (ref "PRO_STM32F4DISCOVERY") (pin "99") (pinfunction "GND_99") (pintype "passive"))
      (node (ref "PRO_SwE7") (pin "COMMON1") (pinfunction "COMMON1_COMMON1") (pintype "passive"))
      (node (ref "PRO_SwE8") (pin "COMMON1") (pinfunction "COMMON1_COMMON1") (pintype "passive"))
      (node (ref "PRO_SwE9") (pin "COMMON1") (pinfunction "COMMON1_COMMON1") (pintype "passive"))
      (node (ref "PRO_UART1") (pin "5") (pinfunction "5_5") (pintype "passive"))
      (node (ref "PRO_UART1") (pin "6") (pinfunction "6_6") (pintype "passive"))
      (node (ref "PRO_UART2") (pin "1") (pinfunction "1_1") (pintype "passive"))
      (node (ref "PRO_Ucan") (pin "2") (pinfunction "VSS_2") (pintype "power_in"))
      (node (ref "PRO_Ucan") (pin "8") (pinfunction "RS_8") (pintype "input"))
      (node (ref "PRO_codDroite") (pin "5") (pinfunction "5_5") (pintype "passive"))
      (node (ref "PRO_codDroite") (pin "6") (pinfunction "6_6") (pintype "passive"))
      (node (ref "PRO_codGauche") (pin "5") (pinfunction "5_5") (pintype "passive"))
      (node (ref "PRO_codGauche") (pin "6") (pinfunction "6_6") (pintype "passive"))
      (node (ref "PRO_currentMot") (pin "1") (pinfunction "1_1") (pintype "passive"))
    )
    (net (code "45") (name "GND_24") (class "Default")
      (node (ref "PRO_CdDtc1") (pin "1") (pinfunction "1_1") (pintype "passive"))
      (node (ref "PRO_CdDtc2") (pin "1") (pinfunction "1_1") (pintype "passive"))
      (node (ref "PRO_CdDtc3") (pin "1") (pinfunction "1_1") (pintype "passive"))
      (node (ref "PRO_CdDtc4") (pin "1") (pinfunction "1_1") (pintype "passive"))
      (node (ref "PRO_DTc1") (pin "1") (pinfunction "1_1") (pintype "passive"))
      (node (ref "PRO_DTc2") (pin "1") (pinfunction "1_1") (pintype "passive"))
      (node (ref "PRO_DTc3") (pin "1") (pinfunction "1_1") (pintype "passive"))
      (node (ref "PRO_DTc4") (pin "1") (pinfunction "1_1") (pintype "passive"))
    )
    (net (code "46") (name "Net-(PRO_DSelftest-A)") (class "Default")
      (node (ref "PRO_DSelftest") (pin "1") (pinfunction "A_1") (pintype "passive"))
      (node (ref "PRO_Rdselftest") (pin "2") (pinfunction "2_2") (pintype "passive"))
    )
    (net (code "47") (name "Net-(PRO_DTc1-Pad2)") (class "Default")
      (node (ref "PRO_DTc1") (pin "2") (pinfunction "2_2") (pintype "passive"))
      (node (ref "PRO_Rdtc1") (pin "2") (pinfunction "2_2") (pintype "passive"))
      (node (ref "PRO_RfDTc1") (pin "1") (pinfunction "1_1") (pintype "passive"))
    )
    (net (code "48") (name "Net-(PRO_DTc2-Pad2)") (class "Default")
      (node (ref "PRO_DTc2") (pin "2") (pinfunction "2_2") (pintype "passive"))
      (node (ref "PRO_Rdtc2") (pin "2") (pinfunction "2_2") (pintype "passive"))
      (node (ref "PRO_RfDTc2") (pin "1") (pinfunction "1_1") (pintype "passive"))
    )
    (net (code "49") (name "Net-(PRO_DTc3-Pad2)") (class "Default")
      (node (ref "PRO_DTc3") (pin "2") (pinfunction "2_2") (pintype "passive"))
      (node (ref "PRO_Rdtc3") (pin "2") (pinfunction "2_2") (pintype "passive"))
      (node (ref "PRO_RfDTc3") (pin "1") (pinfunction "1_1") (pintype "passive"))
    )
    (net (code "50") (name "Net-(PRO_DTc4-Pad2)") (class "Default")
      (node (ref "PRO_DTc4") (pin "2") (pinfunction "2_2") (pintype "passive"))
      (node (ref "PRO_Rdtc4") (pin "2") (pinfunction "2_2") (pintype "passive"))
      (node (ref "PRO_RfDTc4") (pin "1") (pinfunction "1_1") (pintype "passive"))
    )
    (net (code "51") (name "Net-(PRO_Dcan-A)") (class "Default")
      (node (ref "PRO_Dcan") (pin "1") (pinfunction "A_1") (pintype "passive"))
      (node (ref "PRO_Rdcan") (pin "2") (pinfunction "2_2") (pintype "passive"))
    )
    (net (code "52") (name "Net-(PRO_Derror-A)") (class "Default")
      (node (ref "PRO_Derror") (pin "1") (pinfunction "A_1") (pintype "passive"))
      (node (ref "PRO_Rderror") (pin "2") (pinfunction "2_2") (pintype "passive"))
    )
    (net (code "53") (name "Net-(PRO_Drun-A)") (class "Default")
      (node (ref "PRO_Drun") (pin "1") (pinfunction "A_1") (pintype "passive"))
      (node (ref "PRO_Rdrun") (pin "2") (pinfunction "2_2") (pintype "passive"))
    )
    (net (code "54") (name "Net-(PRO_Duart-A)") (class "Default")
      (node (ref "PRO_Duart") (pin "1") (pinfunction "A_1") (pintype "passive"))
      (node (ref "PRO_Rduart") (pin "2") (pinfunction "2_2") (pintype "passive"))
    )
    (net (code "55") (name "Net-(PRO_Duser-A)") (class "Default")
      (node (ref "PRO_Duser") (pin "1") (pinfunction "A_1") (pintype "passive"))
      (node (ref "PRO_Rduser") (pin "2") (pinfunction "2_2") (pintype "passive"))
    )
    (net (code "56") (name "Net-(PRO_RCodDA-Pad2)") (class "Default")
      (node (ref "PRO_RCodDA") (pin "2") (pinfunction "2_2") (pintype "passive"))
      (node (ref "PRO_codDroite") (pin "4") (pinfunction "4_4") (pintype "passive"))
    )
    (net (code "57") (name "Net-(PRO_RCodDB-Pad2)") (class "Default")
      (node (ref "PRO_RCodDB") (pin "2") (pinfunction "2_2") (pintype "passive"))
      (node (ref "PRO_codDroite") (pin "3") (pinfunction "3_3") (pintype "passive"))
    )
    (net (code "58") (name "Net-(PRO_RCodGA-Pad2)") (class "Default")
      (node (ref "PRO_RCodGA") (pin "2") (pinfunction "2_2") (pintype "passive"))
      (node (ref "PRO_codGauche") (pin "4") (pinfunction "4_4") (pintype "passive"))
    )
    (net (code "59") (name "Net-(PRO_RCodGB-Pad2)") (class "Default")
      (node (ref "PRO_RCodGB") (pin "2") (pinfunction "2_2") (pintype "passive"))
      (node (ref "PRO_codGauche") (pin "3") (pinfunction "3_3") (pintype "passive"))
    )
    (net (code "60") (name "Net-(PRO_RpuswE7-Pad1)") (class "Default")
      (node (ref "PRO_RpuswE7") (pin "1") (pinfunction "1_1") (pintype "passive"))
      (node (ref "PRO_RsSwE7") (pin "1") (pinfunction "1_1") (pintype "passive"))
      (node (ref "PRO_SwE7") (pin "NO1") (pinfunction "NO1_NO1") (pintype "passive"))
    )
    (net (code "61") (name "Net-(PRO_RpuswE8-Pad1)") (class "Default")
      (node (ref "PRO_RpuswE8") (pin "1") (pinfunction "1_1") (pintype "passive"))
      (node (ref "PRO_RsSwE8") (pin "1") (pinfunction "1_1") (pintype "passive"))
      (node (ref "PRO_SwE8") (pin "NO1") (pinfunction "NO1_NO1") (pintype "passive"))
    )
    (net (code "62") (name "Net-(PRO_RpuswE9-Pad1)") (class "Default")
      (node (ref "PRO_RpuswE9") (pin "1") (pinfunction "1_1") (pintype "passive"))
      (node (ref "PRO_RsSwE9") (pin "1") (pinfunction "1_1") (pintype "passive"))
      (node (ref "PRO_SwE9") (pin "NO1") (pinfunction "NO1_NO1") (pintype "passive"))
    )
    (net (code "63") (name "unconnected-(PRO_STM32F4DISCOVERY-BOOT0{slash}VPP-Pad71)") (class "Default")
      (node (ref "PRO_STM32F4DISCOVERY") (pin "71") (pinfunction "BOOT0/VPP_71") (pintype "passive+no_connect"))
    )
    (net (code "64") (name "unconnected-(PRO_STM32F4DISCOVERY-NC-Pad48)") (class "Default")
      (node (ref "PRO_STM32F4DISCOVERY") (pin "48") (pinfunction "NC_48") (pintype "passive+no_connect"))
    )
    (net (code "65") (name "unconnected-(PRO_STM32F4DISCOVERY-NRST-Pad6)") (class "Default")
      (node (ref "PRO_STM32F4DISCOVERY") (pin "6") (pinfunction "NRST_6") (pintype "passive+no_connect"))
    )
    (net (code "66") (name "unconnected-(PRO_STM32F4DISCOVERY-PA0-WKUP{slash}USART2_CTS{slash}USART4_TX{slash}ETH_MII_CRS{slash}TIM2_CH1_ETR{slash}TIM5_CH1{slash}TIM8_ETR{slash}ADC123_IN0{slash}WKUP-Pad12)") (class "Default")
      (node (ref "PRO_STM32F4DISCOVERY") (pin "12") (pinfunction "PA0-WKUP/USART2_CTS/USART4_TX/ETH_MII_CRS/TIM2_CH1_ETR/TIM5_CH1/TIM8_ETR/ADC123_IN0/WKUP_12") (pintype "passive+no_connect"))
    )
    (net (code "67") (name "unconnected-(PRO_STM32F4DISCOVERY-PA4{slash}SPI1_NSS{slash}SPI3_NSS{slash}USART2_CK{slash}DCMI_HSYNC{slash}OTG_HS_SOF{slash}I2S3_WS{slash}ADC12_IN4{slash}DAC1_OUT-Pad16)") (class "Default")
      (node (ref "PRO_STM32F4DISCOVERY") (pin "16") (pinfunction "PA4/SPI1_NSS/SPI3_NSS/USART2_CK/DCMI_HSYNC/OTG_HS_SOF/I2S3_WS/ADC12_IN4/DAC1_OUT_16") (pintype "passive+no_connect"))
    )
    (net (code "68") (name "unconnected-(PRO_STM32F4DISCOVERY-PA5{slash}SPI1_SCK{slash}OTG_HS_ULPI_CK{slash}TIM2_CH1_ETR{slash}TIM8_CHIN{slash}ADC12_IN5{slash}DAC2_OUT-Pad15)") (class "Default")
      (node (ref "PRO_STM32F4DISCOVERY") (pin "15") (pinfunction "PA5/SPI1_SCK/OTG_HS_ULPI_CK/TIM2_CH1_ETR/TIM8_CHIN/ADC12_IN5/DAC2_OUT_15") (pintype "passive+no_connect"))
    )
    (net (code "69") (name "unconnected-(PRO_STM32F4DISCOVERY-PA6{slash}SPI1_MISO{slash}TIM8_BKIN{slash}TIM13_CH1{slash}DCMI_PIXCLK{slash}TIM3_CH1{slash}TIM1_BKIN{slash}ADC12_IN6-Pad18)") (class "Default")
      (node (ref "PRO_STM32F4DISCOVERY") (pin "18") (pinfunction "PA6/SPI1_MISO/TIM8_BKIN/TIM13_CH1/DCMI_PIXCLK/TIM3_CH1/TIM1_BKIN/ADC12_IN6_18") (pintype "passive+no_connect"))
    )
    (net (code "70") (name "unconnected-(PRO_STM32F4DISCOVERY-PA7{slash}SPI1_MOSI{slash}TIM8_CH1N{slash}TIM14_CH1TIM3_CH2{slash}ETH_MII_RX_DV{slash}TIM1_CH1N{slash}RMII_CRS_DV{slash}ADC12_IN7-Pad17)") (class "Default")
      (node (ref "PRO_STM32F4DISCOVERY") (pin "17") (pinfunction "PA7/SPI1_MOSI/TIM8_CH1N/TIM14_CH1TIM3_CH2/ETH_MII_RX_DV/TIM1_CH1N/RMII_CRS_DV/ADC12_IN7_17") (pintype "passive+no_connect"))
    )
    (net (code "71") (name "unconnected-(PRO_STM32F4DISCOVERY-PA8{slash}MCO1{slash}USART1_CK{slash}TIM1_CH1{slash}I2C3_SCL{slash}OTG_FS_SOF-Pad93)") (class "Default")
      (node (ref "PRO_STM32F4DISCOVERY") (pin "93") (pinfunction "PA8/MCO1/USART1_CK/TIM1_CH1/I2C3_SCL/OTG_FS_SOF_93") (pintype "passive+no_connect"))
    )
    (net (code "72") (name "unconnected-(PRO_STM32F4DISCOVERY-PA9{slash}USART1_TX{slash}TIM1_CH2{slash}I2C3_SMBA{slash}DCMI_D0{slash}OTG_FS_VBUS-Pad94)") (class "Default")
      (node (ref "PRO_STM32F4DISCOVERY") (pin "94") (pinfunction "PA9/USART1_TX/TIM1_CH2/I2C3_SMBA/DCMI_D0/OTG_FS_VBUS_94") (pintype "passive+no_connect"))
    )
    (net (code "73") (name "unconnected-(PRO_STM32F4DISCOVERY-PA10{slash}USART1_RX{slash}TIM1_CH3{slash}OTG_FS_ID{slash}DCMI_D1-Pad91)") (class "Default")
      (node (ref "PRO_STM32F4DISCOVERY") (pin "91") (pinfunction "PA10/USART1_RX/TIM1_CH3/OTG_FS_ID/DCMI_D1_91") (pintype "passive+no_connect"))
    )
    (net (code "74") (name "unconnected-(PRO_STM32F4DISCOVERY-PA13{slash}JTMS_SWDIO-Pad92)") (class "Default")
      (node (ref "PRO_STM32F4DISCOVERY") (pin "92") (pinfunction "PA13/JTMS_SWDIO_92") (pintype "passive+no_connect"))
    )
    (net (code "75") (name "unconnected-(PRO_STM32F4DISCOVERY-PA14{slash}JTCK_SWCLK-Pad89)") (class "Default")
      (node (ref "PRO_STM32F4DISCOVERY") (pin "89") (pinfunction "PA14/JTCK_SWCLK_89") (pintype "passive+no_connect"))
    )
    (net (code "76") (name "unconnected-(PRO_STM32F4DISCOVERY-PB2-Pad24)") (class "Default")
      (node (ref "PRO_STM32F4DISCOVERY") (pin "24") (pinfunction "PB2_24") (pintype "passive+no_connect"))
    )
    (net (code "77") (name "unconnected-(PRO_STM32F4DISCOVERY-PB3{slash}JTDO{slash}TRACESWO{slash}SPI3_SCK{slash}I2S3_CK{slash}TIM2_CH2{slash}SPI1_SCK-Pad78)") (class "Default")
      (node (ref "PRO_STM32F4DISCOVERY") (pin "78") (pinfunction "PB3/JTDO/TRACESWO/SPI3_SCK/I2S3_CK/TIM2_CH2/SPI1_SCK_78") (pintype "passive+no_connect"))
    )
    (net (code "78") (name "unconnected-(PRO_STM32F4DISCOVERY-PB8{slash}TIM4_CH3{slash}SDIO_D4{slash}TIM10_CH1{slash}DCMI_D6{slash}OTG_FS_SCL{slash}ETH_MII_TXD3{slash}I2C1_SCL{slash}CAN1_RX-Pad69)") (class "Default")
      (node (ref "PRO_STM32F4DISCOVERY") (pin "69") (pinfunction "PB8/TIM4_CH3/SDIO_D4/TIM10_CH1/DCMI_D6/OTG_FS_SCL/ETH_MII_TXD3/I2C1_SCL/CAN1_RX_69") (pintype "passive+no_connect"))
    )
    (net (code "79") (name "unconnected-(PRO_STM32F4DISCOVERY-PB9{slash}SPI2_NSS{slash}I2S2_WS{slash}TIM4_CH4{slash}TIM11_CH1{slash}OTG_FS_SDA{slash}SDIO_D5{slash}DCMI_D7{slash}I2C1_SDA{slash}CAN1_TX-Pad70)") (class "Default")
      (node (ref "PRO_STM32F4DISCOVERY") (pin "70") (pinfunction "PB9/SPI2_NSS/I2S2_WS/TIM4_CH4/TIM11_CH1/OTG_FS_SDA/SDIO_D5/DCMI_D7/I2C1_SDA/CAN1_TX_70") (pintype "passive+no_connect"))
    )
    (net (code "80") (name "unconnected-(PRO_STM32F4DISCOVERY-PB10{slash}SPI2_SCK{slash}I2S2_CK{slash}I2C2_SCL{slash}USART3_TX{slash}OTG_HS_ULPI_D3{slash}ETH_MII_RX_ER{slash}OTG_HS_SCL{slash}TIM2_CH3-Pad34)") (class "Default")
      (node (ref "PRO_STM32F4DISCOVERY") (pin "34") (pinfunction "PB10/SPI2_SCK/I2S2_CK/I2C2_SCL/USART3_TX/OTG_HS_ULPI_D3/ETH_MII_RX_ER/OTG_HS_SCL/TIM2_CH3_34") (pintype "passive+no_connect"))
    )
    (net (code "81") (name "unconnected-(PRO_STM32F4DISCOVERY-PB11{slash}I2C2_SDA{slash}USART3_RX{slash}OTG_HS_ULPI_D4{slash}ETH_RMII_TX_EN{slash}ETH_MII_TX_EN{slash}OTG_HS_SDA{slash}TIM2_CH4-Pad35)") (class "Default")
      (node (ref "PRO_STM32F4DISCOVERY") (pin "35") (pinfunction "PB11/I2C2_SDA/USART3_RX/OTG_HS_ULPI_D4/ETH_RMII_TX_EN/ETH_MII_TX_EN/OTG_HS_SDA/TIM2_CH4_35") (pintype "passive+no_connect"))
    )
    (net (code "82") (name "unconnected-(PRO_STM32F4DISCOVERY-PC0{slash}OTG_HS_ULPI_STP{slash}ADC123_IN10-Pad8)") (class "Default")
      (node (ref "PRO_STM32F4DISCOVERY") (pin "8") (pinfunction "PC0/OTG_HS_ULPI_STP/ADC123_IN10_8") (pintype "passive+no_connect"))
    )
    (net (code "83") (name "unconnected-(PRO_STM32F4DISCOVERY-PC5{slash}ETH_RMII_RX_D1{slash}ETH_MII_RX_D1{slash}ADC12_IN15-Pad19)") (class "Default")
      (node (ref "PRO_STM32F4DISCOVERY") (pin "19") (pinfunction "PC5/ETH_RMII_RX_D1/ETH_MII_RX_D1/ADC12_IN15_19") (pintype "passive+no_connect"))
    )
    (net (code "84") (name "unconnected-(PRO_STM32F4DISCOVERY-PC6{slash}I2S2_MCK{slash}TIM8_CH1{slash}SDIO_D6{slash}USART6_TX{slash}DCMI_D0{slash}TIM3_CH1-Pad97)") (class "Default")
      (node (ref "PRO_STM32F4DISCOVERY") (pin "97") (pinfunction "PC6/I2S2_MCK/TIM8_CH1/SDIO_D6/USART6_TX/DCMI_D0/TIM3_CH1_97") (pintype "passive+no_connect"))
    )
    (net (code "85") (name "unconnected-(PRO_STM32F4DISCOVERY-PC7{slash}I2S3_MCK{slash}TIM8_CH2{slash}SDIO_D7{slash}USART6_RX_DCMI_D1{slash}TIM3_CH2-Pad98)") (class "Default")
      (node (ref "PRO_STM32F4DISCOVERY") (pin "98") (pinfunction "PC7/I2S3_MCK/TIM8_CH2/SDIO_D7/USART6_RX_DCMI_D1/TIM3_CH2_98") (pintype "passive+no_connect"))
    )
    (net (code "86") (name "unconnected-(PRO_STM32F4DISCOVERY-PC10{slash}SPI3_SCK{slash}I2S3_CK{slash}UART4_TX{slash}SDIO_D2{slash}DCMI_D8{slash}USART3_TX-Pad87)") (class "Default")
      (node (ref "PRO_STM32F4DISCOVERY") (pin "87") (pinfunction "PC10/SPI3_SCK/I2S3_CK/UART4_TX/SDIO_D2/DCMI_D8/USART3_TX_87") (pintype "passive+no_connect"))
    )
    (net (code "87") (name "unconnected-(PRO_STM32F4DISCOVERY-PC14{slash}OSC32_IN-Pad59)") (class "Default")
      (node (ref "PRO_STM32F4DISCOVERY") (pin "59") (pinfunction "PC14/OSC32_IN_59") (pintype "passive+no_connect"))
    )
    (net (code "88") (name "unconnected-(PRO_STM32F4DISCOVERY-PC15{slash}OSC32_OUT-Pad60)") (class "Default")
      (node (ref "PRO_STM32F4DISCOVERY") (pin "60") (pinfunction "PC15/OSC32_OUT_60") (pintype "passive+no_connect"))
    )
    (net (code "89") (name "unconnected-(PRO_STM32F4DISCOVERY-PD2{slash}TIM3_ETR{slash}UART5_RXSDIO_CMD{slash}DCMI_D11-Pad84)") (class "Default")
      (node (ref "PRO_STM32F4DISCOVERY") (pin "84") (pinfunction "PD2/TIM3_ETR/UART5_RXSDIO_CMD/DCMI_D11_84") (pintype "passive+no_connect"))
    )
    (net (code "90") (name "unconnected-(PRO_STM32F4DISCOVERY-PD3{slash}FSMC_CLK{slash}USART2_CTS-Pad81)") (class "Default")
      (node (ref "PRO_STM32F4DISCOVERY") (pin "81") (pinfunction "PD3/FSMC_CLK/USART2_CTS_81") (pintype "passive+no_connect"))
    )
    (net (code "91") (name "unconnected-(PRO_STM32F4DISCOVERY-PD4{slash}FSMC_NOE{slash}USART2_RTS-Pad82)") (class "Default")
      (node (ref "PRO_STM32F4DISCOVERY") (pin "82") (pinfunction "PD4/FSMC_NOE/USART2_RTS_82") (pintype "passive+no_connect"))
    )
    (net (code "92") (name "unconnected-(PRO_STM32F4DISCOVERY-PD5{slash}FSMC_NWE{slash}USART2_TX-Pad79)") (class "Default")
      (node (ref "PRO_STM32F4DISCOVERY") (pin "79") (pinfunction "PD5/FSMC_NWE/USART2_TX_79") (pintype "passive+no_connect"))
    )
    (net (code "93") (name "unconnected-(PRO_STM32F4DISCOVERY-PD6{slash}FSMC_NWAIT{slash}USART2_RX-Pad80)") (class "Default")
      (node (ref "PRO_STM32F4DISCOVERY") (pin "80") (pinfunction "PD6/FSMC_NWAIT/USART2_RX_80") (pintype "passive+no_connect"))
    )
    (net (code "94") (name "unconnected-(PRO_STM32F4DISCOVERY-PD7{slash}USART2_CK{slash}FSMC_NE1{slash}FSMC_NCE2-Pad77)") (class "Default")
      (node (ref "PRO_STM32F4DISCOVERY") (pin "77") (pinfunction "PD7/USART2_CK/FSMC_NE1/FSMC_NCE2_77") (pintype "passive+no_connect"))
    )
    (net (code "95") (name "unconnected-(PRO_STM32F4DISCOVERY-PD8{slash}FSMC_D13{slash}USART3_TX-Pad40)") (class "Default")
      (node (ref "PRO_STM32F4DISCOVERY") (pin "40") (pinfunction "PD8/FSMC_D13/USART3_TX_40") (pintype "passive+no_connect"))
    )
    (net (code "96") (name "unconnected-(PRO_STM32F4DISCOVERY-PD9{slash}FSMC_D14{slash}USART3_RX-Pad41)") (class "Default")
      (node (ref "PRO_STM32F4DISCOVERY") (pin "41") (pinfunction "PD9/FSMC_D14/USART3_RX_41") (pintype "passive+no_connect"))
    )
    (net (code "97") (name "unconnected-(PRO_STM32F4DISCOVERY-PE0{slash}TIM4_ETR{slash}FSMC_NBL0{slash}DCMI_D2-Pad67)") (class "Default")
      (node (ref "PRO_STM32F4DISCOVERY") (pin "67") (pinfunction "PE0/TIM4_ETR/FSMC_NBL0/DCMI_D2_67") (pintype "passive+no_connect"))
    )
    (net (code "98") (name "unconnected-(PRO_STM32F4DISCOVERY-PE1{slash}FSMC_NBL1{slash}DCMI_D3-Pad68)") (class "Default")
      (node (ref "PRO_STM32F4DISCOVERY") (pin "68") (pinfunction "PE1/FSMC_NBL1/DCMI_D3_68") (pintype "passive+no_connect"))
    )
    (net (code "99") (name "unconnected-(PRO_STM32F4DISCOVERY-PE2{slash}TRACECLK{slash}FSMC_A23{slash}ETH_MII_TXD3-Pad65)") (class "Default")
      (node (ref "PRO_STM32F4DISCOVERY") (pin "65") (pinfunction "PE2/TRACECLK/FSMC_A23/ETH_MII_TXD3_65") (pintype "passive+no_connect"))
    )
    (net (code "100") (name "unconnected-(PRO_STM32F4DISCOVERY-PE3{slash}TRACED0{slash}FSMC_A19-Pad66)") (class "Default")
      (node (ref "PRO_STM32F4DISCOVERY") (pin "66") (pinfunction "PE3/TRACED0/FSMC_A19_66") (pintype "passive+no_connect"))
    )
    (net (code "101") (name "unconnected-(PRO_STM32F4DISCOVERY-PE4{slash}TRACED1{slash}FSMC_A20{slash}DCMI_D4-Pad63)") (class "Default")
      (node (ref "PRO_STM32F4DISCOVERY") (pin "63") (pinfunction "PE4/TRACED1/FSMC_A20/DCMI_D4_63") (pintype "passive+no_connect"))
    )
    (net (code "102") (name "unconnected-(PRO_STM32F4DISCOVERY-PE5{slash}TRACED2{slash}FSMC_A21{slash}TIM9_CH1{slash}DCMI_D6-Pad64)") (class "Default")
      (node (ref "PRO_STM32F4DISCOVERY") (pin "64") (pinfunction "PE5/TRACED2/FSMC_A21/TIM9_CH1/DCMI_D6_64") (pintype "passive+no_connect"))
    )
    (net (code "103") (name "unconnected-(PRO_STM32F4DISCOVERY-PE6{slash}TRACED3{slash}FSMC_A22{slash}TIM9_CH2{slash}DCMI_D7-Pad61)") (class "Default")
      (node (ref "PRO_STM32F4DISCOVERY") (pin "61") (pinfunction "PE6/TRACED3/FSMC_A22/TIM9_CH2/DCMI_D7_61") (pintype "passive+no_connect"))
    )
    (net (code "104") (name "unconnected-(PRO_STM32F4DISCOVERY-PE10{slash}FSMC_D7{slash}TIM1_CH2N-Pad28)") (class "Default")
      (node (ref "PRO_STM32F4DISCOVERY") (pin "28") (pinfunction "PE10/FSMC_D7/TIM1_CH2N_28") (pintype "passive+no_connect"))
    )
    (net (code "105") (name "unconnected-(PRO_STM32F4DISCOVERY-PE11{slash}FSMC_D8{slash}TIM1_CH2-Pad29)") (class "Default")
      (node (ref "PRO_STM32F4DISCOVERY") (pin "29") (pinfunction "PE11/FSMC_D8/TIM1_CH2_29") (pintype "passive+no_connect"))
    )
    (net (code "106") (name "unconnected-(PRO_STM32F4DISCOVERY-PE13{slash}FSMC_D10{slash}TIM1_CH3-Pad31)") (class "Default")
      (node (ref "PRO_STM32F4DISCOVERY") (pin "31") (pinfunction "PE13/FSMC_D10/TIM1_CH3_31") (pintype "passive+no_connect"))
    )
    (net (code "107") (name "unconnected-(PRO_STM32F4DISCOVERY-PE14{slash}FSMC_D11{slash}TIM1_CH4-Pad32)") (class "Default")
      (node (ref "PRO_STM32F4DISCOVERY") (pin "32") (pinfunction "PE14/FSMC_D11/TIM1_CH4_32") (pintype "passive+no_connect"))
    )
    (net (code "108") (name "unconnected-(PRO_STM32F4DISCOVERY-PE15{slash}FSMC_D12{slash}TIM1_BKIN-Pad33)") (class "Default")
      (node (ref "PRO_STM32F4DISCOVERY") (pin "33") (pinfunction "PE15/FSMC_D12/TIM1_BKIN_33") (pintype "passive+no_connect"))
    )
    (net (code "109") (name "unconnected-(PRO_STM32F4DISCOVERY-PH0{slash}OSC_IN-Pad57)") (class "Default")
      (node (ref "PRO_STM32F4DISCOVERY") (pin "57") (pinfunction "PH0/OSC_IN_57") (pintype "passive+no_connect"))
    )
    (net (code "110") (name "unconnected-(PRO_STM32F4DISCOVERY-PH1{slash}OSC_OUT-Pad58)") (class "Default")
      (node (ref "PRO_STM32F4DISCOVERY") (pin "58") (pinfunction "PH1/OSC_OUT_58") (pintype "passive+no_connect"))
    )
    (net (code "111") (name "unconnected-(PRO_STM32F4DISCOVERY-VDD-Pad3)") (class "Default")
      (node (ref "PRO_STM32F4DISCOVERY") (pin "3") (pinfunction "VDD_3") (pintype "passive+no_connect"))
    )
    (net (code "112") (name "unconnected-(PRO_STM32F4DISCOVERY-VDD-Pad4)") (class "Default")
      (node (ref "PRO_STM32F4DISCOVERY") (pin "4") (pinfunction "VDD_4") (pintype "passive+no_connect"))
    )
    (net (code "113") (name "unconnected-(PRO_STM32F4DISCOVERY-VDD-Pad72)") (class "Default")
      (node (ref "PRO_STM32F4DISCOVERY") (pin "72") (pinfunction "VDD_72") (pintype "passive+no_connect"))
    )
    (net (code "114") (name "unconnected-(PRO_SwE7-PadNC1)") (class "Default")
      (node (ref "PRO_SwE7") (pin "NC1") (pinfunction "NC1_NC1") (pintype "passive+no_connect"))
    )
    (net (code "115") (name "unconnected-(PRO_SwE8-PadNC1)") (class "Default")
      (node (ref "PRO_SwE8") (pin "NC1") (pinfunction "NC1_NC1") (pintype "passive+no_connect"))
    )
    (net (code "116") (name "unconnected-(PRO_SwE9-PadNC1)") (class "Default")
      (node (ref "PRO_SwE9") (pin "NC1") (pinfunction "NC1_NC1") (pintype "passive+no_connect"))
    )
    (net (code "117") (name "unconnected-(PRO_UART1-Pad1)") (class "Default")
      (node (ref "PRO_UART1") (pin "1") (pinfunction "1_1") (pintype "passive+no_connect"))
    )
    (net (code "118") (name "unconnected-(PRO_UART1-Pad2)") (class "Default")
      (node (ref "PRO_UART1") (pin "2") (pinfunction "2_2") (pintype "passive+no_connect"))
    )
    (net (code "119") (name "unconnected-(PRO_Ucan-VREF-Pad5)") (class "Default")
      (node (ref "PRO_Ucan") (pin "5") (pinfunction "VREF_5") (pintype "output+no_connect"))
    )
  )
)
